# 40m_FT8_BD6CR.net
KiCad netlist of a schematic drawn in EAGLE
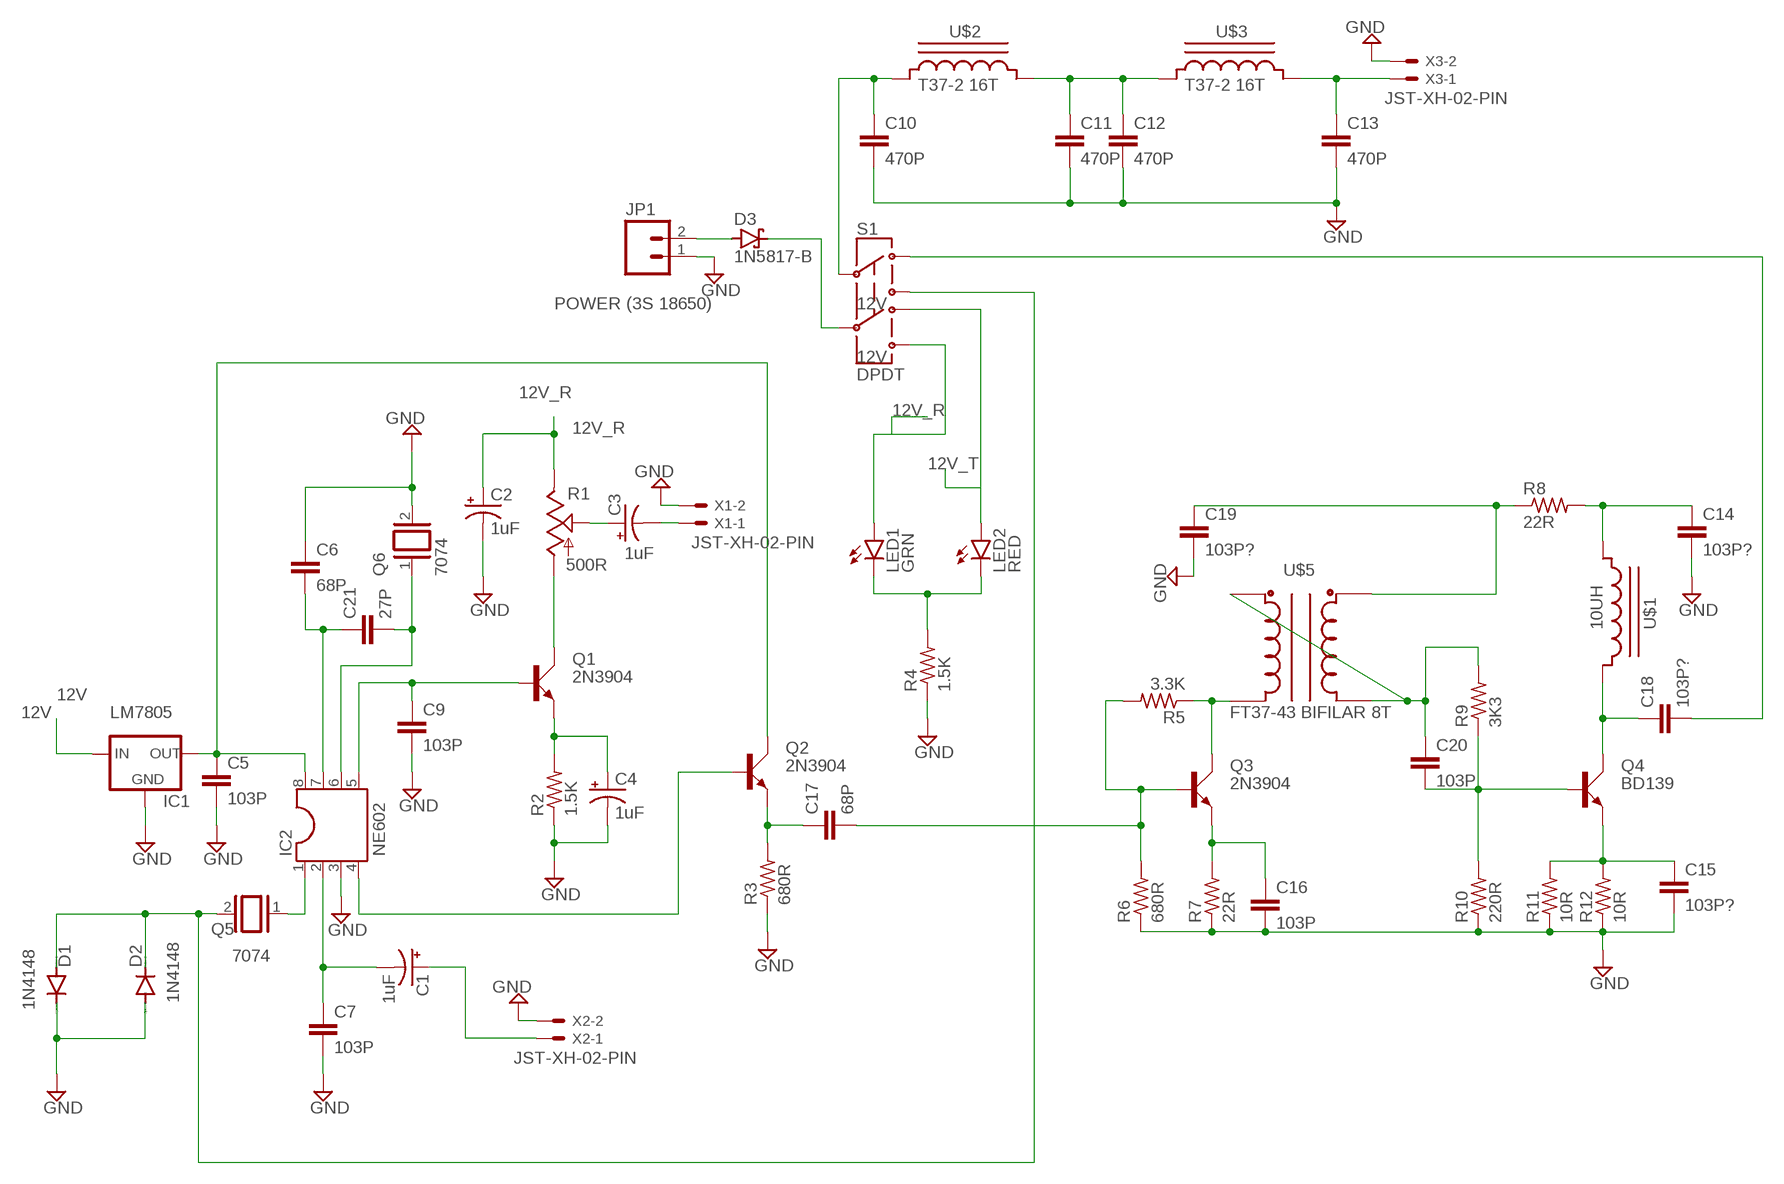
[diagram p0: schematic, sheet 1]

(export (version "E")
  (design (tool "Eeschema 10.0.6"))
  (components
    (comp (ref "C1")
      (value "1uF")
      (footprint "eagle-import:E2-4")
      (libsource (lib "eagle-import") (part "CPOL-USE2-4"))
    )
    (comp (ref "C2")
      (value "1uF")
      (footprint "eagle-import:E2-4")
      (libsource (lib "eagle-import") (part "CPOL-USE2-4"))
    )
    (comp (ref "C3")
      (value "1uF")
      (footprint "eagle-import:E2-4")
      (libsource (lib "eagle-import") (part "CPOL-USE2-4"))
    )
    (comp (ref "C4")
      (value "1uF")
      (footprint "eagle-import:E2-4")
      (libsource (lib "eagle-import") (part "CPOL-USE2-4"))
    )
    (comp (ref "C5")
      (value "103P")
      (footprint "eagle-import:C050-025X075")
      (libsource (lib "eagle-import") (part "C-EU050-025X075"))
    )
    (comp (ref "C6")
      (value "68P")
      (footprint "eagle-import:C050-025X075")
      (libsource (lib "eagle-import") (part "C-EU050-025X075"))
    )
    (comp (ref "C7")
      (value "103P")
      (footprint "eagle-import:C050-025X075")
      (libsource (lib "eagle-import") (part "C-EU050-025X075"))
    )
    (comp (ref "C9")
      (value "103P")
      (footprint "eagle-import:C050-025X075")
      (libsource (lib "eagle-import") (part "C-EU050-025X075"))
    )
    (comp (ref "C10")
      (value "470P")
      (footprint "eagle-import:C050-025X075")
      (libsource (lib "eagle-import") (part "C-EU050-025X075"))
    )
    (comp (ref "C11")
      (value "470P")
      (footprint "eagle-import:C050-025X075")
      (libsource (lib "eagle-import") (part "C-EU050-025X075"))
    )
    (comp (ref "C12")
      (value "470P")
      (footprint "eagle-import:C050-025X075")
      (libsource (lib "eagle-import") (part "C-EU050-025X075"))
    )
    (comp (ref "C13")
      (value "470P")
      (footprint "eagle-import:C050-025X075")
      (libsource (lib "eagle-import") (part "C-EU050-025X075"))
    )
    (comp (ref "C14")
      (value "103P?")
      (footprint "eagle-import:C050-025X075")
      (libsource (lib "eagle-import") (part "C-EU050-025X075"))
    )
    (comp (ref "C15")
      (value "103P?")
      (footprint "eagle-import:C050-025X075")
      (libsource (lib "eagle-import") (part "C-EU050-025X075"))
    )
    (comp (ref "C16")
      (value "103P")
      (footprint "eagle-import:C050-025X075")
      (libsource (lib "eagle-import") (part "C-EU050-025X075"))
    )
    (comp (ref "C17")
      (value "68P")
      (footprint "eagle-import:C050-025X075")
      (libsource (lib "eagle-import") (part "C-EU050-025X075"))
    )
    (comp (ref "C18")
      (value "103P?")
      (footprint "eagle-import:C050-025X075")
      (libsource (lib "eagle-import") (part "C-EU050-025X075"))
    )
    (comp (ref "C19")
      (value "103P?")
      (footprint "eagle-import:C050-025X075")
      (libsource (lib "eagle-import") (part "C-EU050-025X075"))
    )
    (comp (ref "C20")
      (value "103P")
      (footprint "eagle-import:C050-025X075")
      (libsource (lib "eagle-import") (part "C-EU050-025X075"))
    )
    (comp (ref "C21")
      (value "27P")
      (footprint "eagle-import:C050-025X075")
      (libsource (lib "eagle-import") (part "C-EU050-025X075"))
    )
    (comp (ref "D1")
      (value "1N4148")
      (footprint "eagle-import:DO35-10")
      (libsource (lib "eagle-import") (part "1N4148DO35-10"))
    )
    (comp (ref "D2")
      (value "1N4148")
      (footprint "eagle-import:DO35-10")
      (libsource (lib "eagle-import") (part "1N4148DO35-10"))
    )
    (comp (ref "D3")
      (value "1N5817-B")
      (footprint "eagle-import:DO41-7.6")
      (libsource (lib "eagle-import") (part "1N5817-B"))
    )
    (comp (ref "IC1")
      (value "LM7805")
      (footprint "eagle-import:78XXL")
      (libsource (lib "eagle-import") (part "V_REG_78XXSIDE"))
    )
    (comp (ref "IC2")
      (value "NE602")
      (footprint "eagle-import:DIL08")
      (libsource (lib "eagle-import") (part "DIL8"))
    )
    (comp (ref "JP1")
      (value "POWER (3S 18650)")
      (footprint "eagle-import:JST-2-PTH-NS")
      (libsource (lib "eagle-import") (part "M02-JST-2-PTH-NO_SILK"))
    )
    (comp (ref "LED1")
      (value "GRN")
      (footprint "eagle-import:LED_5MM")
      (libsource (lib "eagle-import") (part "LED5MM"))
    )
    (comp (ref "LED2")
      (value "RED")
      (footprint "eagle-import:LED_5MM")
      (libsource (lib "eagle-import") (part "LED5MM"))
    )
    (comp (ref "Q1")
      (value "2N3904")
      (footprint "eagle-import:TO92D")
      (libsource (lib "eagle-import") (part "2N3904"))
    )
    (comp (ref "Q2")
      (value "2N3904")
      (footprint "eagle-import:TO92D")
      (libsource (lib "eagle-import") (part "2N3904"))
    )
    (comp (ref "Q3")
      (value "2N3904")
      (footprint "eagle-import:TO92D")
      (libsource (lib "eagle-import") (part "2N3904"))
    )
    (comp (ref "Q4")
      (value "BD139")
      (footprint "eagle-import:TO92D")
      (libsource (lib "eagle-import") (part "2N3904"))
    )
    (comp (ref "Q5")
      (value "7074")
      (footprint "eagle-import:QS")
      (libsource (lib "eagle-import") (part "XTAL/S"))
    )
    (comp (ref "Q6")
      (value "7074")
      (footprint "eagle-import:QS")
      (libsource (lib "eagle-import") (part "XTAL/S"))
    )
    (comp (ref "R1")
      (value "500R")
      (footprint "eagle-import:CT6")
      (libsource (lib "eagle-import") (part "TRIM_US-CT6"))
    )
    (comp (ref "R2")
      (value "1.5K")
      (footprint "eagle-import:0207_10")
      (libsource (lib "eagle-import") (part "R-US_0207/10"))
    )
    (comp (ref "R3")
      (value "680R")
      (footprint "eagle-import:0207_10")
      (libsource (lib "eagle-import") (part "R-US_0207/10"))
    )
    (comp (ref "R4")
      (value "1.5K")
      (footprint "eagle-import:0207_10")
      (libsource (lib "eagle-import") (part "R-US_0207/10"))
    )
    (comp (ref "R5")
      (value "3.3K")
      (footprint "eagle-import:0207_10")
      (libsource (lib "eagle-import") (part "R-US_0207/10"))
    )
    (comp (ref "R6")
      (value "680R")
      (footprint "eagle-import:0207_10")
      (libsource (lib "eagle-import") (part "R-US_0207/10"))
    )
    (comp (ref "R7")
      (value "22R")
      (footprint "eagle-import:0207_10")
      (libsource (lib "eagle-import") (part "R-US_0207/10"))
    )
    (comp (ref "R8")
      (value "22R")
      (footprint "eagle-import:0207_10")
      (libsource (lib "eagle-import") (part "R-US_0207/10"))
    )
    (comp (ref "R9")
      (value "3K3")
      (footprint "eagle-import:0207_10")
      (libsource (lib "eagle-import") (part "R-US_0207/10"))
    )
    (comp (ref "R10")
      (value "220R")
      (footprint "eagle-import:0207_10")
      (libsource (lib "eagle-import") (part "R-US_0207/10"))
    )
    (comp (ref "R11")
      (value "10R")
      (footprint "eagle-import:0207_10")
      (libsource (lib "eagle-import") (part "R-US_0207/10"))
    )
    (comp (ref "R12")
      (value "10R")
      (footprint "eagle-import:0207_10")
      (libsource (lib "eagle-import") (part "R-US_0207/10"))
    )
    (comp (ref "S1")
      (value "DPDT")
      (footprint "eagle-import:AYZ0202")
      (libsource (lib "eagle-import") (part "SWITCH-DPDTAYZ0202"))
    )
    (comp (ref "U$1")
      (value "10uH")
      (footprint "eagle-import:T37_INDUCTOR")
      (fields (field (name "10UH") "10UH"))
      (libsource (lib "eagle-import") (part "T37_INDUCTOR_FLAT"))
    )
    (comp (ref "U$2")
      (value "T37-2 16T")
      (footprint "eagle-import:T37_INDUCTOR")
      (fields (field (name "T37-2_16T") "T37-2 16T"))
      (libsource (lib "eagle-import") (part "T37_INDUCTOR_FLAT"))
    )
    (comp (ref "U$3")
      (value "T37_INDUCTOR_FLAT")
      (footprint "eagle-import:T37_INDUCTOR")
      (fields (field (name "T37-2_16T") "T37-2 16T"))
      (libsource (lib "eagle-import") (part "T37_INDUCTOR_FLAT"))
    )
    (comp (ref "U$5")
      (value "FT37-43 BIFILAR 8T")
      (footprint "eagle-import:T37_TRANSFORMER")
      (libsource (lib "eagle-import") (part "T37_TRANSFORMER"))
    )
    (comp (ref "X1")
      (value "JST-XH-02-PIN")
      (footprint "eagle-import:JST-XH-02-PACKAGE-LONG-PAD")
      (libsource (lib "eagle-import") (part "JST-XH-02-PIN-LONG-PAD"))
    )
    (comp (ref "X2")
      (value "JST-XH-02-PIN")
      (footprint "eagle-import:JST-XH-02-PACKAGE-LONG-PAD")
      (libsource (lib "eagle-import") (part "JST-XH-02-PIN-LONG-PAD"))
    )
    (comp (ref "X3")
      (value "JST-XH-02-PIN")
      (footprint "eagle-import:JST-XH-02-PACKAGE-LONG-PAD")
      (libsource (lib "eagle-import") (part "JST-XH-02-PIN-LONG-PAD"))
    )
  )
  (nets
    (net (code "1") (name "/12V") (class "Default")
      (node (ref "D3") (pin "C") (pinfunction "C_C") (pintype "passive"))
      (node (ref "IC1") (pin "IN") (pinfunction "IN_IN") (pintype "input"))
      (node (ref "S1") (pin "5") (pinfunction "5_5") (pintype "bidirectional"))
    )
    (net (code "2") (name "/12V_R") (class "Default")
      (node (ref "C2") (pin "+") (pinfunction "+_+") (pintype "passive"))
      (node (ref "LED1") (pin "A") (pinfunction "A_A") (pintype "passive"))
      (node (ref "R1") (pin "E") (pinfunction "E_E") (pintype "passive"))
      (node (ref "S1") (pin "6") (pinfunction "6_6") (pintype "bidirectional"))
    )
    (net (code "3") (name "/12V_T") (class "Default")
      (node (ref "LED2") (pin "A") (pinfunction "A_A") (pintype "passive"))
      (node (ref "S1") (pin "4") (pinfunction "4_4") (pintype "bidirectional"))
    )
    (net (code "4") (name "GND") (class "Default")
      (node (ref "C10") (pin "2") (pinfunction "2_2") (pintype "passive"))
      (node (ref "C11") (pin "2") (pinfunction "2_2") (pintype "passive"))
      (node (ref "C12") (pin "2") (pinfunction "2_2") (pintype "passive"))
      (node (ref "C13") (pin "2") (pinfunction "2_2") (pintype "passive"))
      (node (ref "C14") (pin "2") (pinfunction "2_2") (pintype "passive"))
      (node (ref "C15") (pin "2") (pinfunction "2_2") (pintype "passive"))
      (node (ref "C16") (pin "2") (pinfunction "2_2") (pintype "passive"))
      (node (ref "C19") (pin "2") (pinfunction "2_2") (pintype "passive"))
      (node (ref "C2") (pin "-") (pinfunction "-_-") (pintype "passive"))
      (node (ref "C4") (pin "-") (pinfunction "-_-") (pintype "passive"))
      (node (ref "C5") (pin "2") (pinfunction "2_2") (pintype "passive"))
      (node (ref "C6") (pin "1") (pinfunction "1_1") (pintype "passive"))
      (node (ref "C7") (pin "2") (pinfunction "2_2") (pintype "passive"))
      (node (ref "C9") (pin "2") (pinfunction "2_2") (pintype "passive"))
      (node (ref "D1") (pin "C") (pinfunction "C_C") (pintype "passive"))
      (node (ref "D2") (pin "A") (pinfunction "A_A") (pintype "passive"))
      (node (ref "IC1") (pin "GND") (pinfunction "GND_GND") (pintype "input"))
      (node (ref "IC2") (pin "3") (pinfunction "3_3") (pintype "passive"))
      (node (ref "JP1") (pin "1") (pinfunction "1_1") (pintype "passive"))
      (node (ref "Q6") (pin "2") (pinfunction "2_2") (pintype "passive"))
      (node (ref "R10") (pin "1") (pinfunction "1_1") (pintype "passive"))
      (node (ref "R11") (pin "1") (pinfunction "1_1") (pintype "passive"))
      (node (ref "R12") (pin "1") (pinfunction "1_1") (pintype "passive"))
      (node (ref "R2") (pin "1") (pinfunction "1_1") (pintype "passive"))
      (node (ref "R3") (pin "1") (pinfunction "1_1") (pintype "passive"))
      (node (ref "R4") (pin "1") (pinfunction "1_1") (pintype "passive"))
      (node (ref "R6") (pin "1") (pinfunction "1_1") (pintype "passive"))
      (node (ref "R7") (pin "1") (pinfunction "1_1") (pintype "passive"))
      (node (ref "X1") (pin "2") (pinfunction "S_2") (pintype "passive"))
      (node (ref "X2") (pin "2") (pinfunction "S_2") (pintype "passive"))
      (node (ref "X3") (pin "2") (pinfunction "S_2") (pintype "passive"))
    )
    (net (code "5") (name "Net-(C1-Pad-)") (class "Default")
      (node (ref "C1") (pin "-") (pinfunction "-_-") (pintype "passive"))
      (node (ref "C7") (pin "1") (pinfunction "1_1") (pintype "passive"))
      (node (ref "IC2") (pin "2") (pinfunction "2_2") (pintype "passive"))
    )
    (net (code "6") (name "Net-(C3-Pad+)") (class "Default")
      (node (ref "C3") (pin "+") (pinfunction "+_+") (pintype "passive"))
      (node (ref "R1") (pin "S") (pinfunction "S_S") (pintype "passive"))
    )
    (net (code "7") (name "Net-(C4-Pad+)") (class "Default")
      (node (ref "C4") (pin "+") (pinfunction "+_+") (pintype "passive"))
      (node (ref "Q1") (pin "E") (pinfunction "E_E") (pintype "passive"))
      (node (ref "R2") (pin "2") (pinfunction "2_2") (pintype "passive"))
    )
    (net (code "8") (name "Net-(C5-Pad1)") (class "Default")
      (node (ref "C5") (pin "1") (pinfunction "1_1") (pintype "passive"))
      (node (ref "IC1") (pin "OUT") (pinfunction "OUT_OUT") (pintype "output"))
      (node (ref "IC2") (pin "8") (pinfunction "8_8") (pintype "passive"))
      (node (ref "Q2") (pin "C") (pinfunction "C_C") (pintype "passive"))
    )
    (net (code "9") (name "Net-(C9-Pad1)") (class "Default")
      (node (ref "C9") (pin "1") (pinfunction "1_1") (pintype "passive"))
      (node (ref "IC2") (pin "5") (pinfunction "5_5") (pintype "passive"))
      (node (ref "Q1") (pin "B") (pinfunction "B_B") (pintype "passive"))
    )
    (net (code "10") (name "Net-(C10-Pad1)") (class "Default")
      (node (ref "C10") (pin "1") (pinfunction "1_1") (pintype "passive"))
      (node (ref "S1") (pin "2") (pinfunction "2_2") (pintype "bidirectional"))
      (node (ref "U$2") (pin "CB") (pinfunction "CB_CB") (pintype "bidirectional"))
    )
    (net (code "11") (name "Net-(C11-Pad1)") (class "Default")
      (node (ref "C11") (pin "1") (pinfunction "1_1") (pintype "passive"))
      (node (ref "C12") (pin "1") (pinfunction "1_1") (pintype "passive"))
      (node (ref "U$2") (pin "CA") (pinfunction "CA_CA") (pintype "bidirectional"))
      (node (ref "U$3") (pin "CB") (pinfunction "CB_CB") (pintype "bidirectional"))
    )
    (net (code "12") (name "Net-(C14-Pad1)") (class "Default")
      (node (ref "C14") (pin "1") (pinfunction "1_1") (pintype "passive"))
      (node (ref "R8") (pin "2") (pinfunction "2_2") (pintype "passive"))
      (node (ref "U$1") (pin "CB") (pinfunction "CB_CB") (pintype "bidirectional"))
    )
    (net (code "13") (name "Net-(C15-Pad1)") (class "Default")
      (node (ref "C15") (pin "1") (pinfunction "1_1") (pintype "passive"))
      (node (ref "Q4") (pin "E") (pinfunction "E_E") (pintype "passive"))
      (node (ref "R11") (pin "2") (pinfunction "2_2") (pintype "passive"))
      (node (ref "R12") (pin "2") (pinfunction "2_2") (pintype "passive"))
    )
    (net (code "14") (name "Net-(C16-Pad1)") (class "Default")
      (node (ref "C16") (pin "1") (pinfunction "1_1") (pintype "passive"))
      (node (ref "Q3") (pin "E") (pinfunction "E_E") (pintype "passive"))
      (node (ref "R7") (pin "2") (pinfunction "2_2") (pintype "passive"))
    )
    (net (code "15") (name "Net-(C17-Pad1)") (class "Default")
      (node (ref "C17") (pin "1") (pinfunction "1_1") (pintype "passive"))
      (node (ref "Q2") (pin "E") (pinfunction "E_E") (pintype "passive"))
      (node (ref "R3") (pin "2") (pinfunction "2_2") (pintype "passive"))
    )
    (net (code "16") (name "Net-(C17-Pad2)") (class "Default")
      (node (ref "C17") (pin "2") (pinfunction "2_2") (pintype "passive"))
      (node (ref "Q3") (pin "B") (pinfunction "B_B") (pintype "passive"))
      (node (ref "R5") (pin "2") (pinfunction "2_2") (pintype "passive"))
      (node (ref "R6") (pin "2") (pinfunction "2_2") (pintype "passive"))
    )
    (net (code "17") (name "Net-(C18-Pad1)") (class "Default")
      (node (ref "C18") (pin "1") (pinfunction "1_1") (pintype "passive"))
      (node (ref "Q4") (pin "C") (pinfunction "C_C") (pintype "passive"))
      (node (ref "U$1") (pin "CA") (pinfunction "CA_CA") (pintype "bidirectional"))
    )
    (net (code "18") (name "Net-(C18-Pad2)") (class "Default")
      (node (ref "C18") (pin "2") (pinfunction "2_2") (pintype "passive"))
      (node (ref "S1") (pin "1") (pinfunction "1_1") (pintype "bidirectional"))
    )
    (net (code "19") (name "Net-(C19-Pad1)") (class "Default")
      (node (ref "C19") (pin "1") (pinfunction "1_1") (pintype "passive"))
      (node (ref "R8") (pin "1") (pinfunction "1_1") (pintype "passive"))
      (node (ref "U$5") (pin "C2B") (pinfunction "C2B_C2B") (pintype "bidirectional"))
    )
    (net (code "20") (name "Net-(C20-Pad1)") (class "Default")
      (node (ref "C20") (pin "1") (pinfunction "1_1") (pintype "passive"))
      (node (ref "R9") (pin "2") (pinfunction "2_2") (pintype "passive"))
      (node (ref "U$5") (pin "C1B") (pinfunction "C1B_C1B") (pintype "bidirectional"))
      (node (ref "U$5") (pin "C2A") (pinfunction "C2A_C2A") (pintype "bidirectional"))
    )
    (net (code "21") (name "Net-(C20-Pad2)") (class "Default")
      (node (ref "C20") (pin "2") (pinfunction "2_2") (pintype "passive"))
      (node (ref "Q4") (pin "B") (pinfunction "B_B") (pintype "passive"))
      (node (ref "R10") (pin "2") (pinfunction "2_2") (pintype "passive"))
      (node (ref "R9") (pin "1") (pinfunction "1_1") (pintype "passive"))
    )
    (net (code "22") (name "Net-(C21-Pad1)") (class "Default")
      (node (ref "C21") (pin "1") (pinfunction "1_1") (pintype "passive"))
      (node (ref "C6") (pin "2") (pinfunction "2_2") (pintype "passive"))
      (node (ref "IC2") (pin "7") (pinfunction "7_7") (pintype "passive"))
    )
    (net (code "23") (name "Net-(C21-Pad2)") (class "Default")
      (node (ref "C21") (pin "2") (pinfunction "2_2") (pintype "passive"))
      (node (ref "IC2") (pin "6") (pinfunction "6_6") (pintype "passive"))
      (node (ref "Q6") (pin "1") (pinfunction "1_1") (pintype "passive"))
    )
    (net (code "24") (name "Net-(D1-PadA)") (class "Default")
      (node (ref "D1") (pin "A") (pinfunction "A_A") (pintype "passive"))
      (node (ref "D2") (pin "C") (pinfunction "C_C") (pintype "passive"))
      (node (ref "Q5") (pin "2") (pinfunction "2_2") (pintype "passive"))
      (node (ref "S1") (pin "3") (pinfunction "3_3") (pintype "bidirectional"))
    )
    (net (code "25") (name "Net-(D3-PadA)") (class "Default")
      (node (ref "D3") (pin "A") (pinfunction "A_A") (pintype "passive"))
      (node (ref "JP1") (pin "2") (pinfunction "2_2") (pintype "passive"))
    )
    (net (code "26") (name "Net-(IC2-Pad1)") (class "Default")
      (node (ref "IC2") (pin "1") (pinfunction "1_1") (pintype "passive"))
      (node (ref "Q5") (pin "1") (pinfunction "1_1") (pintype "passive"))
    )
    (net (code "27") (name "Net-(IC2-Pad4)") (class "Default")
      (node (ref "IC2") (pin "4") (pinfunction "4_4") (pintype "passive"))
      (node (ref "Q2") (pin "B") (pinfunction "B_B") (pintype "passive"))
    )
    (net (code "28") (name "Net-(LED1-C)") (class "Default")
      (node (ref "LED1") (pin "K") (pinfunction "C_K") (pintype "passive"))
      (node (ref "LED2") (pin "K") (pinfunction "C_K") (pintype "passive"))
      (node (ref "R4") (pin "2") (pinfunction "2_2") (pintype "passive"))
    )
    (net (code "29") (name "Net-(Q1-PadC)") (class "Default")
      (node (ref "Q1") (pin "C") (pinfunction "C_C") (pintype "passive"))
      (node (ref "R1") (pin "A") (pinfunction "A_A") (pintype "passive"))
    )
    (net (code "30") (name "Net-(Q3-PadC)") (class "Default")
      (node (ref "Q3") (pin "C") (pinfunction "C_C") (pintype "passive"))
      (node (ref "R5") (pin "1") (pinfunction "1_1") (pintype "passive"))
      (node (ref "U$5") (pin "C1A") (pinfunction "C1A_C1A") (pintype "bidirectional"))
    )
    (net (code "31") (name "Net-(X1A-S)") (class "Default")
      (node (ref "C3") (pin "-") (pinfunction "-_-") (pintype "passive"))
      (node (ref "X1") (pin "1") (pinfunction "S_1") (pintype "passive"))
    )
    (net (code "32") (name "Net-(X2A-S)") (class "Default")
      (node (ref "C1") (pin "+") (pinfunction "+_+") (pintype "passive"))
      (node (ref "X2") (pin "1") (pinfunction "S_1") (pintype "passive"))
    )
    (net (code "33") (name "Net-(X3A-S)") (class "Default")
      (node (ref "C13") (pin "1") (pinfunction "1_1") (pintype "passive"))
      (node (ref "U$3") (pin "CA") (pinfunction "CA_CA") (pintype "bidirectional"))
      (node (ref "X3") (pin "1") (pinfunction "S_1") (pintype "passive"))
    )
  )
)
